# NFC.net
KiCad netlist of a schematic drawn in Altium Designer
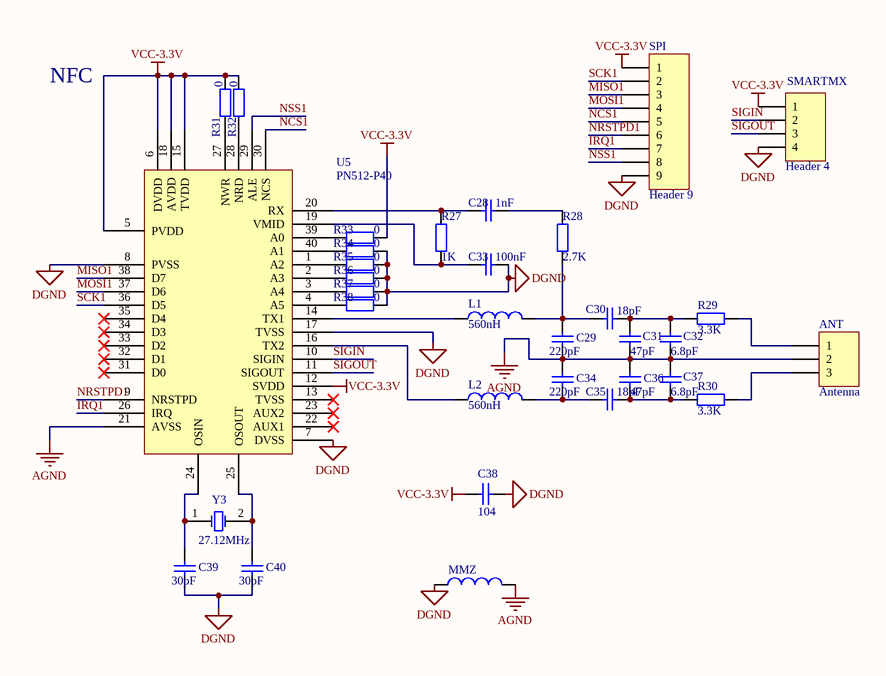
[diagram p0: NFC.SchDoc]

(export (version "E")
  (design (tool "Eeschema 10.0.6"))
  (components
    (comp (ref "ANT")
      (value "Antenna")
      (footprint "HDR1X3")
      (description "Header, 3-Pin")
      (fields (field (name "PUBLISHER") "Altium Limited"))
      (libsource (lib "Miscellaneous Connectors") (part "Header 3"))
    )
    (comp (ref "C28")
      (value "1nF")
      (footprint "1608[0603]")
      (description "Capacitor")
      (fields (field (name "Comment") "Cap") (field (name "PUBLISHER") "Altium Limited"))
      (libsource (lib "common") (part "Cap"))
    )
    (comp (ref "C29")
      (value "220pF")
      (footprint "1608[0603]")
      (description "Capacitor")
      (fields (field (name "Comment") "Cap") (field (name "PUBLISHER") "Altium Limited"))
      (libsource (lib "common") (part "Cap"))
    )
    (comp (ref "C30")
      (value "18pF")
      (footprint "1608[0603]")
      (description "Capacitor")
      (fields (field (name "Comment") "Cap") (field (name "PUBLISHER") "Altium Limited"))
      (libsource (lib "common") (part "Cap"))
    )
    (comp (ref "C31")
      (value "47pF")
      (footprint "1608[0603]")
      (description "Capacitor")
      (fields (field (name "Comment") "Cap") (field (name "PUBLISHER") "Altium Limited"))
      (libsource (lib "common") (part "Cap"))
    )
    (comp (ref "C32")
      (value "6.8pF")
      (footprint "1608[0603]")
      (description "Capacitor")
      (fields (field (name "Comment") "Cap") (field (name "PUBLISHER") "Altium Limited"))
      (libsource (lib "common") (part "Cap"))
    )
    (comp (ref "C33")
      (value "100nF")
      (footprint "1608[0603]")
      (description "Capacitor")
      (fields (field (name "Comment") "Cap") (field (name "PUBLISHER") "Altium Limited"))
      (libsource (lib "common") (part "Cap"))
    )
    (comp (ref "C34")
      (value "220pF")
      (footprint "1608[0603]")
      (description "Capacitor")
      (fields (field (name "Comment") "Cap") (field (name "PUBLISHER") "Altium Limited"))
      (libsource (lib "common") (part "Cap"))
    )
    (comp (ref "C35")
      (value "18pF")
      (footprint "1608[0603]")
      (description "Capacitor")
      (fields (field (name "Comment") "Cap") (field (name "PUBLISHER") "Altium Limited"))
      (libsource (lib "common") (part "Cap"))
    )
    (comp (ref "C36")
      (value "47pF")
      (footprint "1608[0603]")
      (description "Capacitor")
      (fields (field (name "Comment") "Cap") (field (name "PUBLISHER") "Altium Limited"))
      (libsource (lib "common") (part "Cap"))
    )
    (comp (ref "C37")
      (value "6.8pF")
      (footprint "1608[0603]")
      (description "Capacitor")
      (fields (field (name "Comment") "Cap") (field (name "PUBLISHER") "Altium Limited"))
      (libsource (lib "common") (part "Cap"))
    )
    (comp (ref "C38")
      (value "104")
      (footprint "1608[0603]")
      (description "Capacitor")
      (fields (field (name "Comment") "Cap") (field (name "PUBLISHER") "Altium Limited"))
      (libsource (lib "common") (part "Cap"))
    )
    (comp (ref "C39")
      (value "30pF")
      (footprint "1608[0603]")
      (description "Capacitor")
      (fields (field (name "Comment") "Cap") (field (name "PUBLISHER") "Altium Limited"))
      (libsource (lib "common") (part "Cap"))
    )
    (comp (ref "C40")
      (value "30pF")
      (footprint "1608[0603]")
      (description "Capacitor")
      (fields (field (name "Comment") "Cap") (field (name "PUBLISHER") "Altium Limited"))
      (libsource (lib "common") (part "Cap"))
    )
    (comp (ref "L1")
      (value "560nH")
      (footprint "2012_Chip")
      (description "Inductor")
      (fields (field (name "PUBLISHER") "Altium Limited"))
      (libsource (lib "Miscellaneous Devices") (part "Inductor"))
    )
    (comp (ref "L2")
      (value "560nH")
      (footprint "2012_Chip")
      (description "Inductor")
      (fields (field (name "PUBLISHER") "Altium Limited"))
      (libsource (lib "Miscellaneous Devices") (part "Inductor"))
    )
    (comp (ref "MMZ")
      (value "Inductor")
      (footprint "2012_Chip")
      (fields (field (name "PUBLISHER") "Altium Limited"))
      (libsource (lib "Miscellaneous Devices") (part "Inductor"))
    )
    (comp (ref "R27")
      (value "1K")
      (footprint "1608[0603]")
      (description "Resistor")
      (fields (field (name "Comment") "RES") (field (name "PUBLISHER") "Altium Limited"))
      (libsource (lib "") (part "RES_1"))
    )
    (comp (ref "R28")
      (value "2.7K")
      (footprint "1608[0603]")
      (description "Resistor")
      (fields (field (name "Comment") "RES") (field (name "PUBLISHER") "Altium Limited"))
      (libsource (lib "") (part "RES_1"))
    )
    (comp (ref "R29")
      (value "3.3K")
      (footprint "1608[0603]")
      (description "Resistor")
      (fields (field (name "Comment") "RES") (field (name "PUBLISHER") "Altium Limited"))
      (libsource (lib "common") (part "RES"))
    )
    (comp (ref "R30")
      (value "3.3K")
      (footprint "1608[0603]")
      (description "Resistor")
      (fields (field (name "Comment") "RES") (field (name "PUBLISHER") "Altium Limited"))
      (libsource (lib "common") (part "RES"))
    )
    (comp (ref "R31")
      (value "0")
      (footprint "1608[0603]")
      (description "Resistor")
      (fields (field (name "Comment") "RES") (field (name "PUBLISHER") "Altium Limited"))
      (libsource (lib "") (part "RES_1"))
    )
    (comp (ref "R32")
      (value "0")
      (footprint "1608[0603]")
      (description "Resistor")
      (fields (field (name "Comment") "RES") (field (name "PUBLISHER") "Altium Limited"))
      (libsource (lib "") (part "RES_1"))
    )
    (comp (ref "R33")
      (value "0")
      (footprint "1608[0603]")
      (description "Resistor")
      (fields (field (name "Comment") "RES") (field (name "PUBLISHER") "Altium Limited"))
      (libsource (lib "common") (part "RES"))
    )
    (comp (ref "R34")
      (value "0")
      (footprint "1608[0603]")
      (description "Resistor")
      (fields (field (name "Comment") "RES") (field (name "PUBLISHER") "Altium Limited"))
      (libsource (lib "common") (part "RES"))
    )
    (comp (ref "R35")
      (value "0")
      (footprint "1608[0603]")
      (description "Resistor")
      (fields (field (name "Comment") "RES") (field (name "PUBLISHER") "Altium Limited"))
      (libsource (lib "common") (part "RES"))
    )
    (comp (ref "R36")
      (value "0")
      (footprint "1608[0603]")
      (description "Resistor")
      (fields (field (name "Comment") "RES") (field (name "PUBLISHER") "Altium Limited"))
      (libsource (lib "common") (part "RES"))
    )
    (comp (ref "R37")
      (value "0")
      (footprint "1608[0603]")
      (description "Resistor")
      (fields (field (name "Comment") "RES") (field (name "PUBLISHER") "Altium Limited"))
      (libsource (lib "common") (part "RES"))
    )
    (comp (ref "R38")
      (value "0")
      (footprint "1608[0603]")
      (description "Resistor")
      (fields (field (name "Comment") "RES") (field (name "PUBLISHER") "Altium Limited"))
      (libsource (lib "common") (part "RES"))
    )
    (comp (ref "SMARTMX")
      (value "Header 4")
      (footprint "HDR1X4")
      (description "Header, 4-Pin")
      (fields (field (name "PUBLISHER") "Altium Limited"))
      (libsource (lib "Miscellaneous Connectors") (part "Header 4"))
    )
    (comp (ref "SPI")
      (value "Header 9")
      (footprint "HDR1X9")
      (description "Header, 9-Pin")
      (fields (field (name "PUBLISHER") "Altium Limited"))
      (libsource (lib "Miscellaneous Connectors") (part "Header 9"))
    )
    (comp (ref "U5")
      (value "PN512-P40")
      (footprint "QFN50P600X600-40VN")
      (libsource (lib "*") (part "PN511-P40"))
    )
    (comp (ref "Y3")
      (value "27.12MHz")
      (footprint "XTAL")
      (description "Crystal Oscillator")
      (fields (field (name "PUBLISHER") "Altium Limited"))
      (libsource (lib "common") (part "XTAL"))
    )
  )
  (nets
    (net (code "1") (name "/IRQ1") (class "Default")
      (node (ref "SPI") (pin "7") (pinfunction "7_7") (pintype "passive"))
      (node (ref "U5") (pin "26") (pinfunction "IRQ_26") (pintype "passive"))
    )
    (net (code "2") (name "/MISO1") (class "Default")
      (node (ref "SPI") (pin "3") (pinfunction "3_3") (pintype "passive"))
      (node (ref "U5") (pin "38") (pinfunction "D7_38") (pintype "passive"))
    )
    (net (code "3") (name "/MOSI1") (class "Default")
      (node (ref "SPI") (pin "4") (pinfunction "4_4") (pintype "passive"))
      (node (ref "U5") (pin "37") (pinfunction "D6_37") (pintype "passive"))
    )
    (net (code "4") (name "/NCS1") (class "Default")
      (node (ref "SPI") (pin "5") (pinfunction "5_5") (pintype "passive"))
      (node (ref "U5") (pin "30") (pinfunction "NCS_30") (pintype "passive"))
    )
    (net (code "5") (name "/NRSTPD1") (class "Default")
      (node (ref "SPI") (pin "6") (pinfunction "6_6") (pintype "passive"))
      (node (ref "U5") (pin "9") (pinfunction "NRSTPD_9") (pintype "passive"))
    )
    (net (code "6") (name "/NSS1") (class "Default")
      (node (ref "SPI") (pin "8") (pinfunction "8_8") (pintype "passive"))
      (node (ref "U5") (pin "29") (pinfunction "ALE_29") (pintype "passive"))
    )
    (net (code "7") (name "/SCK1") (class "Default")
      (node (ref "SPI") (pin "2") (pinfunction "2_2") (pintype "passive"))
      (node (ref "U5") (pin "36") (pinfunction "D5_36") (pintype "passive"))
    )
    (net (code "8") (name "/SIGIN") (class "Default")
      (node (ref "SMARTMX") (pin "2") (pinfunction "2_2") (pintype "passive"))
      (node (ref "U5") (pin "10") (pinfunction "SIGIN_10") (pintype "passive"))
    )
    (net (code "9") (name "/SIGOUT") (class "Default")
      (node (ref "SMARTMX") (pin "3") (pinfunction "3_3") (pintype "passive"))
      (node (ref "U5") (pin "11") (pinfunction "SIGOUT_11") (pintype "passive"))
    )
    (net (code "10") (name "AGND") (class "Default")
      (node (ref "ANT") (pin "2") (pinfunction "2_2") (pintype "passive"))
      (node (ref "C29") (pin "1") (pinfunction "1_1") (pintype "passive"))
      (node (ref "C31") (pin "1") (pinfunction "1_1") (pintype "passive"))
      (node (ref "C32") (pin "1") (pinfunction "1_1") (pintype "passive"))
      (node (ref "C34") (pin "2") (pinfunction "2_2") (pintype "passive"))
      (node (ref "C36") (pin "2") (pinfunction "2_2") (pintype "passive"))
      (node (ref "C37") (pin "2") (pinfunction "2_2") (pintype "passive"))
      (node (ref "MMZ") (pin "2") (pinfunction "2_2") (pintype "passive"))
      (node (ref "U5") (pin "21") (pinfunction "AVSS_21") (pintype "passive"))
    )
    (net (code "11") (name "DGND") (class "Default")
      (node (ref "C33") (pin "2") (pinfunction "2_2") (pintype "passive"))
      (node (ref "C38") (pin "1") (pinfunction "1_1") (pintype "passive"))
      (node (ref "C39") (pin "1") (pinfunction "1_1") (pintype "passive"))
      (node (ref "C40") (pin "1") (pinfunction "1_1") (pintype "passive"))
      (node (ref "MMZ") (pin "1") (pinfunction "1_1") (pintype "passive"))
      (node (ref "R34") (pin "1") (pinfunction "1_1") (pintype "passive"))
      (node (ref "R35") (pin "1") (pinfunction "1_1") (pintype "passive"))
      (node (ref "R36") (pin "1") (pinfunction "1_1") (pintype "passive"))
      (node (ref "R37") (pin "1") (pinfunction "1_1") (pintype "passive"))
      (node (ref "R38") (pin "1") (pinfunction "1_1") (pintype "passive"))
      (node (ref "SMARTMX") (pin "4") (pinfunction "4_4") (pintype "passive"))
      (node (ref "SPI") (pin "9") (pinfunction "9_9") (pintype "passive"))
      (node (ref "U5") (pin "17") (pinfunction "TVSS_17") (pintype "passive"))
      (node (ref "U5") (pin "7") (pinfunction "DVSS_7") (pintype "passive"))
      (node (ref "U5") (pin "8") (pinfunction "PVSS_8") (pintype "passive"))
    )
    (net (code "12") (name "Net-(ANT-Pad1)") (class "Default")
      (node (ref "ANT") (pin "1") (pinfunction "1_1") (pintype "passive"))
      (node (ref "R29") (pin "1") (pinfunction "1_1") (pintype "passive"))
    )
    (net (code "13") (name "Net-(ANT-Pad3)") (class "Default")
      (node (ref "ANT") (pin "3") (pinfunction "3_3") (pintype "passive"))
      (node (ref "R30") (pin "1") (pinfunction "1_1") (pintype "passive"))
    )
    (net (code "14") (name "Net-(C28-Pad2)") (class "Default")
      (node (ref "C28") (pin "2") (pinfunction "2_2") (pintype "passive"))
      (node (ref "R28") (pin "2") (pinfunction "2_2") (pintype "passive"))
    )
    (net (code "15") (name "Net-(C29-Pad2)") (class "Default")
      (node (ref "C29") (pin "2") (pinfunction "2_2") (pintype "passive"))
      (node (ref "C30") (pin "1") (pinfunction "1_1") (pintype "passive"))
      (node (ref "L1") (pin "2") (pinfunction "2_2") (pintype "passive"))
      (node (ref "R28") (pin "1") (pinfunction "1_1") (pintype "passive"))
    )
    (net (code "16") (name "Net-(C30-Pad2)") (class "Default")
      (node (ref "C30") (pin "2") (pinfunction "2_2") (pintype "passive"))
      (node (ref "C31") (pin "2") (pinfunction "2_2") (pintype "passive"))
      (node (ref "C32") (pin "2") (pinfunction "2_2") (pintype "passive"))
      (node (ref "R29") (pin "2") (pinfunction "2_2") (pintype "passive"))
    )
    (net (code "17") (name "Net-(C34-Pad1)") (class "Default")
      (node (ref "C34") (pin "1") (pinfunction "1_1") (pintype "passive"))
      (node (ref "C35") (pin "1") (pinfunction "1_1") (pintype "passive"))
      (node (ref "L2") (pin "2") (pinfunction "2_2") (pintype "passive"))
    )
    (net (code "18") (name "Net-(C35-Pad2)") (class "Default")
      (node (ref "C35") (pin "2") (pinfunction "2_2") (pintype "passive"))
      (node (ref "C36") (pin "1") (pinfunction "1_1") (pintype "passive"))
      (node (ref "C37") (pin "1") (pinfunction "1_1") (pintype "passive"))
      (node (ref "R30") (pin "2") (pinfunction "2_2") (pintype "passive"))
    )
    (net (code "19") (name "Net-(U5-A0)") (class "Default")
      (node (ref "R33") (pin "2") (pinfunction "2_2") (pintype "passive"))
      (node (ref "U5") (pin "39") (pinfunction "A0_39") (pintype "passive"))
    )
    (net (code "20") (name "Net-(U5-A1)") (class "Default")
      (node (ref "R34") (pin "2") (pinfunction "2_2") (pintype "passive"))
      (node (ref "U5") (pin "40") (pinfunction "A1_40") (pintype "passive"))
    )
    (net (code "21") (name "Net-(U5-A2)") (class "Default")
      (node (ref "R35") (pin "2") (pinfunction "2_2") (pintype "passive"))
      (node (ref "U5") (pin "1") (pinfunction "A2_1") (pintype "passive"))
    )
    (net (code "22") (name "Net-(U5-A3)") (class "Default")
      (node (ref "R36") (pin "2") (pinfunction "2_2") (pintype "passive"))
      (node (ref "U5") (pin "2") (pinfunction "A3_2") (pintype "passive"))
    )
    (net (code "23") (name "Net-(U5-A4)") (class "Default")
      (node (ref "R37") (pin "2") (pinfunction "2_2") (pintype "passive"))
      (node (ref "U5") (pin "3") (pinfunction "A4_3") (pintype "passive"))
    )
    (net (code "24") (name "Net-(U5-A5)") (class "Default")
      (node (ref "R38") (pin "2") (pinfunction "2_2") (pintype "passive"))
      (node (ref "U5") (pin "4") (pinfunction "A5_4") (pintype "passive"))
    )
    (net (code "25") (name "Net-(U5-NRD)") (class "Default")
      (node (ref "R32") (pin "1") (pinfunction "1_1") (pintype "passive"))
      (node (ref "U5") (pin "28") (pinfunction "NRD_28") (pintype "passive"))
    )
    (net (code "26") (name "Net-(U5-NWR)") (class "Default")
      (node (ref "R31") (pin "1") (pinfunction "1_1") (pintype "passive"))
      (node (ref "U5") (pin "27") (pinfunction "NWR_27") (pintype "passive"))
    )
    (net (code "27") (name "Net-(U5-OSIN)") (class "Default")
      (node (ref "C39") (pin "2") (pinfunction "2_2") (pintype "passive"))
      (node (ref "U5") (pin "24") (pinfunction "OSIN_24") (pintype "passive"))
      (node (ref "Y3") (pin "1") (pinfunction "OSC1_1") (pintype "passive"))
    )
    (net (code "28") (name "Net-(U5-OSOUT)") (class "Default")
      (node (ref "C40") (pin "2") (pinfunction "2_2") (pintype "passive"))
      (node (ref "U5") (pin "25") (pinfunction "OSOUT_25") (pintype "passive"))
      (node (ref "Y3") (pin "2") (pinfunction "OSC2_2") (pintype "passive"))
    )
    (net (code "29") (name "Net-(U5-RX)") (class "Default")
      (node (ref "C28") (pin "1") (pinfunction "1_1") (pintype "passive"))
      (node (ref "R27") (pin "2") (pinfunction "2_2") (pintype "passive"))
      (node (ref "U5") (pin "20") (pinfunction "RX_20") (pintype "passive"))
    )
    (net (code "30") (name "Net-(U5-TX1)") (class "Default")
      (node (ref "L1") (pin "1") (pinfunction "1_1") (pintype "passive"))
      (node (ref "U5") (pin "14") (pinfunction "TX1_14") (pintype "passive"))
    )
    (net (code "31") (name "Net-(U5-TX2)") (class "Default")
      (node (ref "L2") (pin "1") (pinfunction "1_1") (pintype "passive"))
      (node (ref "U5") (pin "16") (pinfunction "TX2_16") (pintype "passive"))
    )
    (net (code "32") (name "Net-(U5-VMID)") (class "Default")
      (node (ref "C33") (pin "1") (pinfunction "1_1") (pintype "passive"))
      (node (ref "R27") (pin "1") (pinfunction "1_1") (pintype "passive"))
      (node (ref "U5") (pin "19") (pinfunction "VMID_19") (pintype "passive"))
    )
    (net (code "33") (name "VCC-3.3V") (class "Default")
      (node (ref "C38") (pin "2") (pinfunction "2_2") (pintype "passive"))
      (node (ref "R31") (pin "2") (pinfunction "2_2") (pintype "passive"))
      (node (ref "R32") (pin "2") (pinfunction "2_2") (pintype "passive"))
      (node (ref "R33") (pin "1") (pinfunction "1_1") (pintype "passive"))
      (node (ref "SMARTMX") (pin "1") (pinfunction "1_1") (pintype "passive"))
      (node (ref "SPI") (pin "1") (pinfunction "1_1") (pintype "passive"))
      (node (ref "U5") (pin "12") (pinfunction "SVDD_12") (pintype "passive"))
      (node (ref "U5") (pin "15") (pinfunction "TVDD_15") (pintype "passive"))
      (node (ref "U5") (pin "18") (pinfunction "AVDD_18") (pintype "passive"))
      (node (ref "U5") (pin "5") (pinfunction "PVDD_5") (pintype "passive"))
      (node (ref "U5") (pin "6") (pinfunction "DVDD_6") (pintype "passive"))
    )
    (net (code "34") (name "unconnected-(U5-AUX1-Pad22)") (class "Default")
      (node (ref "U5") (pin "22") (pinfunction "AUX1_22") (pintype "passive+no_connect"))
    )
    (net (code "35") (name "unconnected-(U5-AUX2-Pad23)") (class "Default")
      (node (ref "U5") (pin "23") (pinfunction "AUX2_23") (pintype "passive+no_connect"))
    )
    (net (code "36") (name "unconnected-(U5-D0-Pad31)") (class "Default")
      (node (ref "U5") (pin "31") (pinfunction "D0_31") (pintype "passive+no_connect"))
    )
    (net (code "37") (name "unconnected-(U5-D1-Pad32)") (class "Default")
      (node (ref "U5") (pin "32") (pinfunction "D1_32") (pintype "passive+no_connect"))
    )
    (net (code "38") (name "unconnected-(U5-D2-Pad33)") (class "Default")
      (node (ref "U5") (pin "33") (pinfunction "D2_33") (pintype "passive+no_connect"))
    )
    (net (code "39") (name "unconnected-(U5-D3-Pad34)") (class "Default")
      (node (ref "U5") (pin "34") (pinfunction "D3_34") (pintype "passive+no_connect"))
    )
    (net (code "40") (name "unconnected-(U5-D4-Pad35)") (class "Default")
      (node (ref "U5") (pin "35") (pinfunction "D4_35") (pintype "passive+no_connect"))
    )
    (net (code "41") (name "unconnected-(U5-TVSS-Pad13)") (class "Default")
      (node (ref "U5") (pin "13") (pinfunction "TVSS_13") (pintype "passive+no_connect"))
    )
  )
)
